# RGB.net
KiCad netlist of a schematic drawn in EAGLE
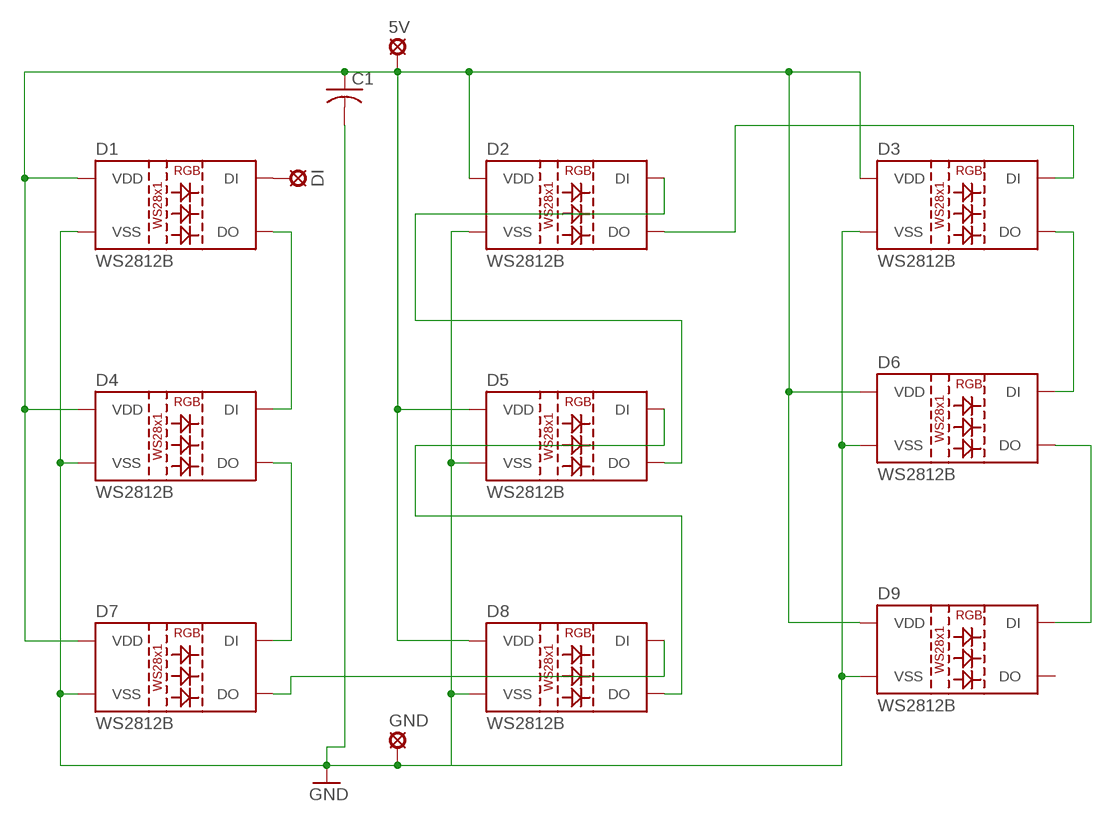
[diagram p0: schematic, sheet 1]

(export (version "E")
  (design (tool "Eeschema 10.0.6"))
  (components
    (comp (ref "5V")
      (value "LSP11")
      (footprint "eagle-import:LSP11")
      (libsource (lib "eagle-import") (part "LSP11"))
    )
    (comp (ref "C1")
      (value "C-USC0805K")
      (footprint "eagle-import:C0805K")
      (libsource (lib "eagle-import") (part "C-USC0805K"))
    )
    (comp (ref "D1")
      (value "WS2812B")
      (footprint "eagle-import:WS2812B")
      (libsource (lib "eagle-import") (part "WS2812B"))
    )
    (comp (ref "D2")
      (value "WS2812B")
      (footprint "eagle-import:WS2812B")
      (libsource (lib "eagle-import") (part "WS2812B"))
    )
    (comp (ref "D3")
      (value "WS2812B")
      (footprint "eagle-import:WS2812B")
      (libsource (lib "eagle-import") (part "WS2812B"))
    )
    (comp (ref "D4")
      (value "WS2812B")
      (footprint "eagle-import:WS2812B")
      (libsource (lib "eagle-import") (part "WS2812B"))
    )
    (comp (ref "D5")
      (value "WS2812B")
      (footprint "eagle-import:WS2812B")
      (libsource (lib "eagle-import") (part "WS2812B"))
    )
    (comp (ref "D6")
      (value "WS2812B")
      (footprint "eagle-import:WS2812B")
      (libsource (lib "eagle-import") (part "WS2812B"))
    )
    (comp (ref "D7")
      (value "WS2812B")
      (footprint "eagle-import:WS2812B")
      (libsource (lib "eagle-import") (part "WS2812B"))
    )
    (comp (ref "D8")
      (value "WS2812B")
      (footprint "eagle-import:WS2812B")
      (libsource (lib "eagle-import") (part "WS2812B"))
    )
    (comp (ref "D9")
      (value "WS2812B")
      (footprint "eagle-import:WS2812B")
      (libsource (lib "eagle-import") (part "WS2812B"))
    )
    (comp (ref "DI")
      (value "LSP11")
      (footprint "eagle-import:LSP11")
      (libsource (lib "eagle-import") (part "LSP11"))
    )
    (comp (ref "GND")
      (value "LSP11")
      (footprint "eagle-import:LSP11")
      (libsource (lib "eagle-import") (part "LSP11"))
    )
  )
  (nets
    (net (code "1") (name "GND") (class "Default")
      (node (ref "C1") (pin "2") (pinfunction "2_2") (pintype "passive"))
      (node (ref "D1") (pin "3") (pinfunction "VSS_3") (pintype "bidirectional"))
      (node (ref "D2") (pin "3") (pinfunction "VSS_3") (pintype "bidirectional"))
      (node (ref "D3") (pin "3") (pinfunction "VSS_3") (pintype "bidirectional"))
      (node (ref "D4") (pin "3") (pinfunction "VSS_3") (pintype "bidirectional"))
      (node (ref "D5") (pin "3") (pinfunction "VSS_3") (pintype "bidirectional"))
      (node (ref "D6") (pin "3") (pinfunction "VSS_3") (pintype "bidirectional"))
      (node (ref "D7") (pin "3") (pinfunction "VSS_3") (pintype "bidirectional"))
      (node (ref "D8") (pin "3") (pinfunction "VSS_3") (pintype "bidirectional"))
      (node (ref "D9") (pin "3") (pinfunction "VSS_3") (pintype "bidirectional"))
      (node (ref "GND") (pin "MP") (pinfunction "MP_MP") (pintype "passive"))
    )
    (net (code "2") (name "Net-(D1-DI)") (class "Default")
      (node (ref "D1") (pin "4") (pinfunction "DI_4") (pintype "bidirectional"))
      (node (ref "DI") (pin "MP") (pinfunction "MP_MP") (pintype "passive"))
    )
    (net (code "3") (name "Net-(D1-DO)") (class "Default")
      (node (ref "D1") (pin "2") (pinfunction "DO_2") (pintype "bidirectional"))
      (node (ref "D4") (pin "4") (pinfunction "DI_4") (pintype "bidirectional"))
    )
    (net (code "4") (name "Net-(D1-VDD)") (class "Default")
      (node (ref "5V") (pin "MP") (pinfunction "MP_MP") (pintype "passive"))
      (node (ref "C1") (pin "1") (pinfunction "1_1") (pintype "passive"))
      (node (ref "D1") (pin "1") (pinfunction "VDD_1") (pintype "bidirectional"))
      (node (ref "D2") (pin "1") (pinfunction "VDD_1") (pintype "bidirectional"))
      (node (ref "D3") (pin "1") (pinfunction "VDD_1") (pintype "bidirectional"))
      (node (ref "D4") (pin "1") (pinfunction "VDD_1") (pintype "bidirectional"))
      (node (ref "D5") (pin "1") (pinfunction "VDD_1") (pintype "bidirectional"))
      (node (ref "D6") (pin "1") (pinfunction "VDD_1") (pintype "bidirectional"))
      (node (ref "D7") (pin "1") (pinfunction "VDD_1") (pintype "bidirectional"))
      (node (ref "D8") (pin "1") (pinfunction "VDD_1") (pintype "bidirectional"))
      (node (ref "D9") (pin "1") (pinfunction "VDD_1") (pintype "bidirectional"))
    )
    (net (code "5") (name "Net-(D2-DI)") (class "Default")
      (node (ref "D2") (pin "4") (pinfunction "DI_4") (pintype "bidirectional"))
      (node (ref "D5") (pin "2") (pinfunction "DO_2") (pintype "bidirectional"))
    )
    (net (code "6") (name "Net-(D2-DO)") (class "Default")
      (node (ref "D2") (pin "2") (pinfunction "DO_2") (pintype "bidirectional"))
      (node (ref "D3") (pin "4") (pinfunction "DI_4") (pintype "bidirectional"))
    )
    (net (code "7") (name "Net-(D3-DO)") (class "Default")
      (node (ref "D3") (pin "2") (pinfunction "DO_2") (pintype "bidirectional"))
      (node (ref "D6") (pin "4") (pinfunction "DI_4") (pintype "bidirectional"))
    )
    (net (code "8") (name "Net-(D4-DO)") (class "Default")
      (node (ref "D4") (pin "2") (pinfunction "DO_2") (pintype "bidirectional"))
      (node (ref "D7") (pin "4") (pinfunction "DI_4") (pintype "bidirectional"))
    )
    (net (code "9") (name "Net-(D5-DI)") (class "Default")
      (node (ref "D5") (pin "4") (pinfunction "DI_4") (pintype "bidirectional"))
      (node (ref "D8") (pin "2") (pinfunction "DO_2") (pintype "bidirectional"))
    )
    (net (code "10") (name "Net-(D6-DO)") (class "Default")
      (node (ref "D6") (pin "2") (pinfunction "DO_2") (pintype "bidirectional"))
      (node (ref "D9") (pin "4") (pinfunction "DI_4") (pintype "bidirectional"))
    )
    (net (code "11") (name "Net-(D7-DO)") (class "Default")
      (node (ref "D7") (pin "2") (pinfunction "DO_2") (pintype "bidirectional"))
      (node (ref "D8") (pin "4") (pinfunction "DI_4") (pintype "bidirectional"))
    )
    (net (code "12") (name "unconnected-(D9-DO-Pad2)") (class "Default")
      (node (ref "D9") (pin "2") (pinfunction "DO_2") (pintype "bidirectional"))
    )
  )
)
